# Sheet2.net
KiCad netlist of a schematic drawn in Altium Designer
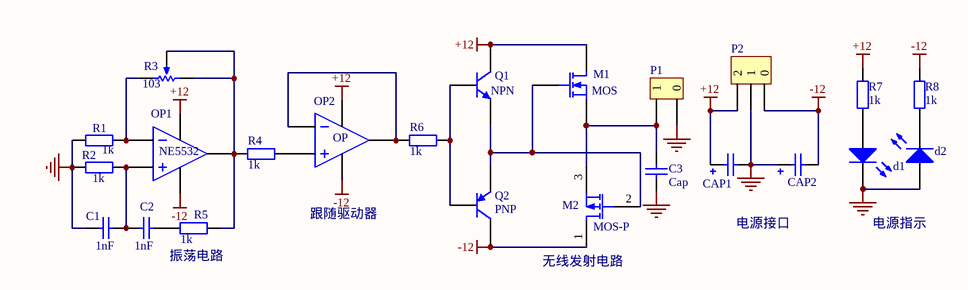
[diagram p0: Sheet2.SchDoc]

(export (version "E")
  (design (tool "Eeschema 10.0.6"))
  (components
    (comp (ref "C1") (value "1nF") (footprint "Cap") (libsource (lib "标准封装") (part "Cap")))
    (comp (ref "C2") (value "1nF") (footprint "Cap") (libsource (lib "标准封装") (part "Cap")))
    (comp (ref "C3") (value "Cap") (footprint "C") (libsource (lib "标准封装") (part "Cap")))
    (comp (ref "CAP1") (value "电解小电容") (footprint "电解小电容") (libsource (lib "标准封装") (part "电解小电容")))
    (comp (ref "CAP2") (value "电解小电容") (footprint "电解小电容") (libsource (lib "标准封装") (part "电解小电容")))
    (comp (ref "d1") (value "LED") (footprint "LED") (libsource (lib "标准封装") (part "LED")))
    (comp (ref "d2") (value "LED") (footprint "LED") (libsource (lib "标准封装") (part "LED")))
    (comp (ref "M1") (value "MOS") (footprint "MOS1") (libsource (lib "标准封装") (part "MOS")))
    (comp (ref "M2") (value "MOS-P") (footprint "MOS-P") (libsource (lib "标准封装") (part "MOS-P")))
    (comp (ref "OP1") (value "NE5532") (footprint "OP") (libsource (lib "标准封装") (part "OP")))
    (comp (ref "OP2") (value "OP") (footprint "OP") (libsource (lib "标准封装") (part "OP")))
    (comp (ref "P1") (value "双孔压线器") (footprint "双孔压线器") (libsource (lib "标准封装") (part "双孔压线器")))
    (comp (ref "P2") (value "三脚压线器") (footprint "三脚压线器") (libsource (lib "标准封装") (part "三脚压线器")))
    (comp (ref "Q1") (value "NPN") (footprint "npn - duplicate") (libsource (lib "标准封装") (part "NPN")))
    (comp (ref "Q2") (value "PNP") (footprint "pnp - duplicate") (libsource (lib "标准封装") (part "PNP")))
    (comp (ref "R1")
      (value "电阻")
      (footprint "电阻")
      (fields (field (name "ALTIUM_UNNAMED_1") "1k"))
      (libsource (lib "标准封装") (part "电阻"))
    )
    (comp (ref "R2")
      (value "电阻")
      (footprint "电阻")
      (fields (field (name "ALTIUM_UNNAMED_1") "1k"))
      (libsource (lib "") (part "电阻_2"))
    )
    (comp (ref "R3")
      (value "滑动变阻器")
      (footprint "滑动变阻器")
      (fields (field (name "ALTIUM_UNNAMED_1") "103"))
      (libsource (lib "标准封装") (part "滑动变阻器"))
    )
    (comp (ref "R4")
      (value "电阻")
      (footprint "电阻")
      (fields (field (name "ALTIUM_UNNAMED_1") "1k"))
      (libsource (lib "标准封装") (part "电阻"))
    )
    (comp (ref "R5")
      (value "电阻")
      (footprint "电阻")
      (fields (field (name "ALTIUM_UNNAMED_1") "1k"))
      (libsource (lib "标准封装") (part "电阻"))
    )
    (comp (ref "R6")
      (value "电阻")
      (footprint "电阻")
      (fields (field (name "ALTIUM_UNNAMED_1") "1k"))
      (libsource (lib "标准封装") (part "电阻"))
    )
    (comp (ref "R7")
      (value "电阻")
      (footprint "电阻")
      (fields (field (name "ALTIUM_UNNAMED_1") "1k"))
      (libsource (lib "") (part "电阻_1"))
    )
    (comp (ref "R8")
      (value "电阻")
      (footprint "电阻")
      (fields (field (name "ALTIUM_UNNAMED_1") "1k"))
      (libsource (lib "") (part "电阻_1"))
    )
  )
  (nets
    (net (code "1") (name "+12") (class "Default")
      (node (ref "CAP1") (pin "2") (pinfunction "2_2") (pintype "passive"))
      (node (ref "M1") (pin "1") (pinfunction "D_1") (pintype "passive"))
      (node (ref "OP1") (pin "4") (pinfunction "3_4") (pintype "passive"))
      (node (ref "OP2") (pin "4") (pinfunction "3_4") (pintype "passive"))
      (node (ref "P2") (pin "2") (pinfunction "2_2") (pintype "passive"))
      (node (ref "Q1") (pin "1") (pinfunction "C_1") (pintype "passive"))
      (node (ref "R7") (pin "2") (pinfunction "2_2") (pintype "passive"))
    )
    (net (code "2") (name "-12") (class "Default")
      (node (ref "CAP2") (pin "1") (pinfunction "1_1") (pintype "passive"))
      (node (ref "M2") (pin "1") (pinfunction "D_1") (pintype "passive"))
      (node (ref "OP1") (pin "3") (pinfunction "2_3") (pintype "passive"))
      (node (ref "OP2") (pin "3") (pinfunction "2_3") (pintype "passive"))
      (node (ref "P2") (pin "0") (pinfunction "0_0") (pintype "passive"))
      (node (ref "Q2") (pin "1") (pinfunction "C_1") (pintype "passive"))
      (node (ref "R8") (pin "2") (pinfunction "2_2") (pintype "passive"))
    )
    (net (code "3") (name "GND") (class "Default")
      (node (ref "C1") (pin "2") (pinfunction "2_2") (pintype "passive"))
      (node (ref "C3") (pin "2") (pinfunction "2_2") (pintype "passive"))
      (node (ref "CAP1") (pin "1") (pinfunction "1_1") (pintype "passive"))
      (node (ref "CAP2") (pin "2") (pinfunction "2_2") (pintype "passive"))
      (node (ref "P1") (pin "0") (pinfunction "0_0") (pintype "passive"))
      (node (ref "P2") (pin "1") (pinfunction "1_1") (pintype "passive"))
      (node (ref "R1") (pin "1") (pinfunction "1_1") (pintype "passive"))
      (node (ref "R2") (pin "2") (pinfunction "2_2") (pintype "passive"))
      (node (ref "d1") (pin "2") (pinfunction "K_2") (pintype "passive"))
      (node (ref "d2") (pin "1") (pinfunction "A_1") (pintype "passive"))
    )
    (net (code "4") (name "Net-(C2-Pad2)") (class "Default")
      (node (ref "C2") (pin "2") (pinfunction "2_2") (pintype "passive"))
      (node (ref "R5") (pin "1") (pinfunction "1_1") (pintype "passive"))
    )
    (net (code "5") (name "Net-(M1-G)") (class "Default")
      (node (ref "M1") (pin "2") (pinfunction "G_2") (pintype "passive"))
      (node (ref "M2") (pin "2") (pinfunction "G_2") (pintype "passive"))
      (node (ref "Q1") (pin "3") (pinfunction "E_3") (pintype "passive"))
      (node (ref "Q2") (pin "3") (pinfunction "E_3") (pintype "passive"))
    )
    (net (code "6") (name "Net-(M1-S)") (class "Default")
      (node (ref "C3") (pin "1") (pinfunction "1_1") (pintype "passive"))
      (node (ref "M1") (pin "3") (pinfunction "S_3") (pintype "passive"))
      (node (ref "M2") (pin "3") (pinfunction "S_3") (pintype "passive"))
      (node (ref "P1") (pin "1") (pinfunction "1_1") (pintype "passive"))
    )
    (net (code "7") (name "Net-(OP1-0)") (class "Default")
      (node (ref "OP1") (pin "1") (pinfunction "0_1") (pintype "passive"))
      (node (ref "R1") (pin "2") (pinfunction "2_2") (pintype "passive"))
      (node (ref "R3") (pin "2") (pinfunction "BOT_2") (pintype "passive"))
    )
    (net (code "8") (name "Net-(OP1-1)") (class "Default")
      (node (ref "C1") (pin "1") (pinfunction "1_1") (pintype "passive"))
      (node (ref "C2") (pin "1") (pinfunction "1_1") (pintype "passive"))
      (node (ref "OP1") (pin "2") (pinfunction "1_2") (pintype "passive"))
      (node (ref "R2") (pin "1") (pinfunction "1_1") (pintype "passive"))
    )
    (net (code "9") (name "Net-(OP2-0)") (class "Default")
      (node (ref "OP2") (pin "1") (pinfunction "0_1") (pintype "passive"))
      (node (ref "OP2") (pin "5") (pinfunction "5_5") (pintype "passive"))
      (node (ref "R6") (pin "1") (pinfunction "1_1") (pintype "passive"))
    )
    (net (code "10") (name "Net-(OP2-1)") (class "Default")
      (node (ref "OP2") (pin "2") (pinfunction "1_2") (pintype "passive"))
      (node (ref "R4") (pin "2") (pinfunction "2_2") (pintype "passive"))
    )
    (net (code "11") (name "Net-(Q1-B)") (class "Default")
      (node (ref "Q1") (pin "2") (pinfunction "B_2") (pintype "passive"))
      (node (ref "Q2") (pin "2") (pinfunction "B_2") (pintype "passive"))
      (node (ref "R6") (pin "2") (pinfunction "2_2") (pintype "passive"))
    )
    (net (code "12") (name "Net-(R3-TAP)") (class "Default")
      (node (ref "OP1") (pin "5") (pinfunction "5_5") (pintype "passive"))
      (node (ref "R3") (pin "1") (pinfunction "TOP_1") (pintype "passive"))
      (node (ref "R3") (pin "3") (pinfunction "TAP_3") (pintype "passive"))
      (node (ref "R4") (pin "1") (pinfunction "1_1") (pintype "passive"))
      (node (ref "R5") (pin "2") (pinfunction "2_2") (pintype "passive"))
    )
    (net (code "13") (name "Net-(d1-A)") (class "Default")
      (node (ref "R7") (pin "1") (pinfunction "1_1") (pintype "passive"))
      (node (ref "d1") (pin "1") (pinfunction "A_1") (pintype "passive"))
    )
    (net (code "14") (name "Net-(d2-K)") (class "Default")
      (node (ref "R8") (pin "1") (pinfunction "1_1") (pintype "passive"))
      (node (ref "d2") (pin "2") (pinfunction "K_2") (pintype "passive"))
    )
  )
)
